# PCB.net
KiCad netlist of a schematic drawn in EasyEDA Pro
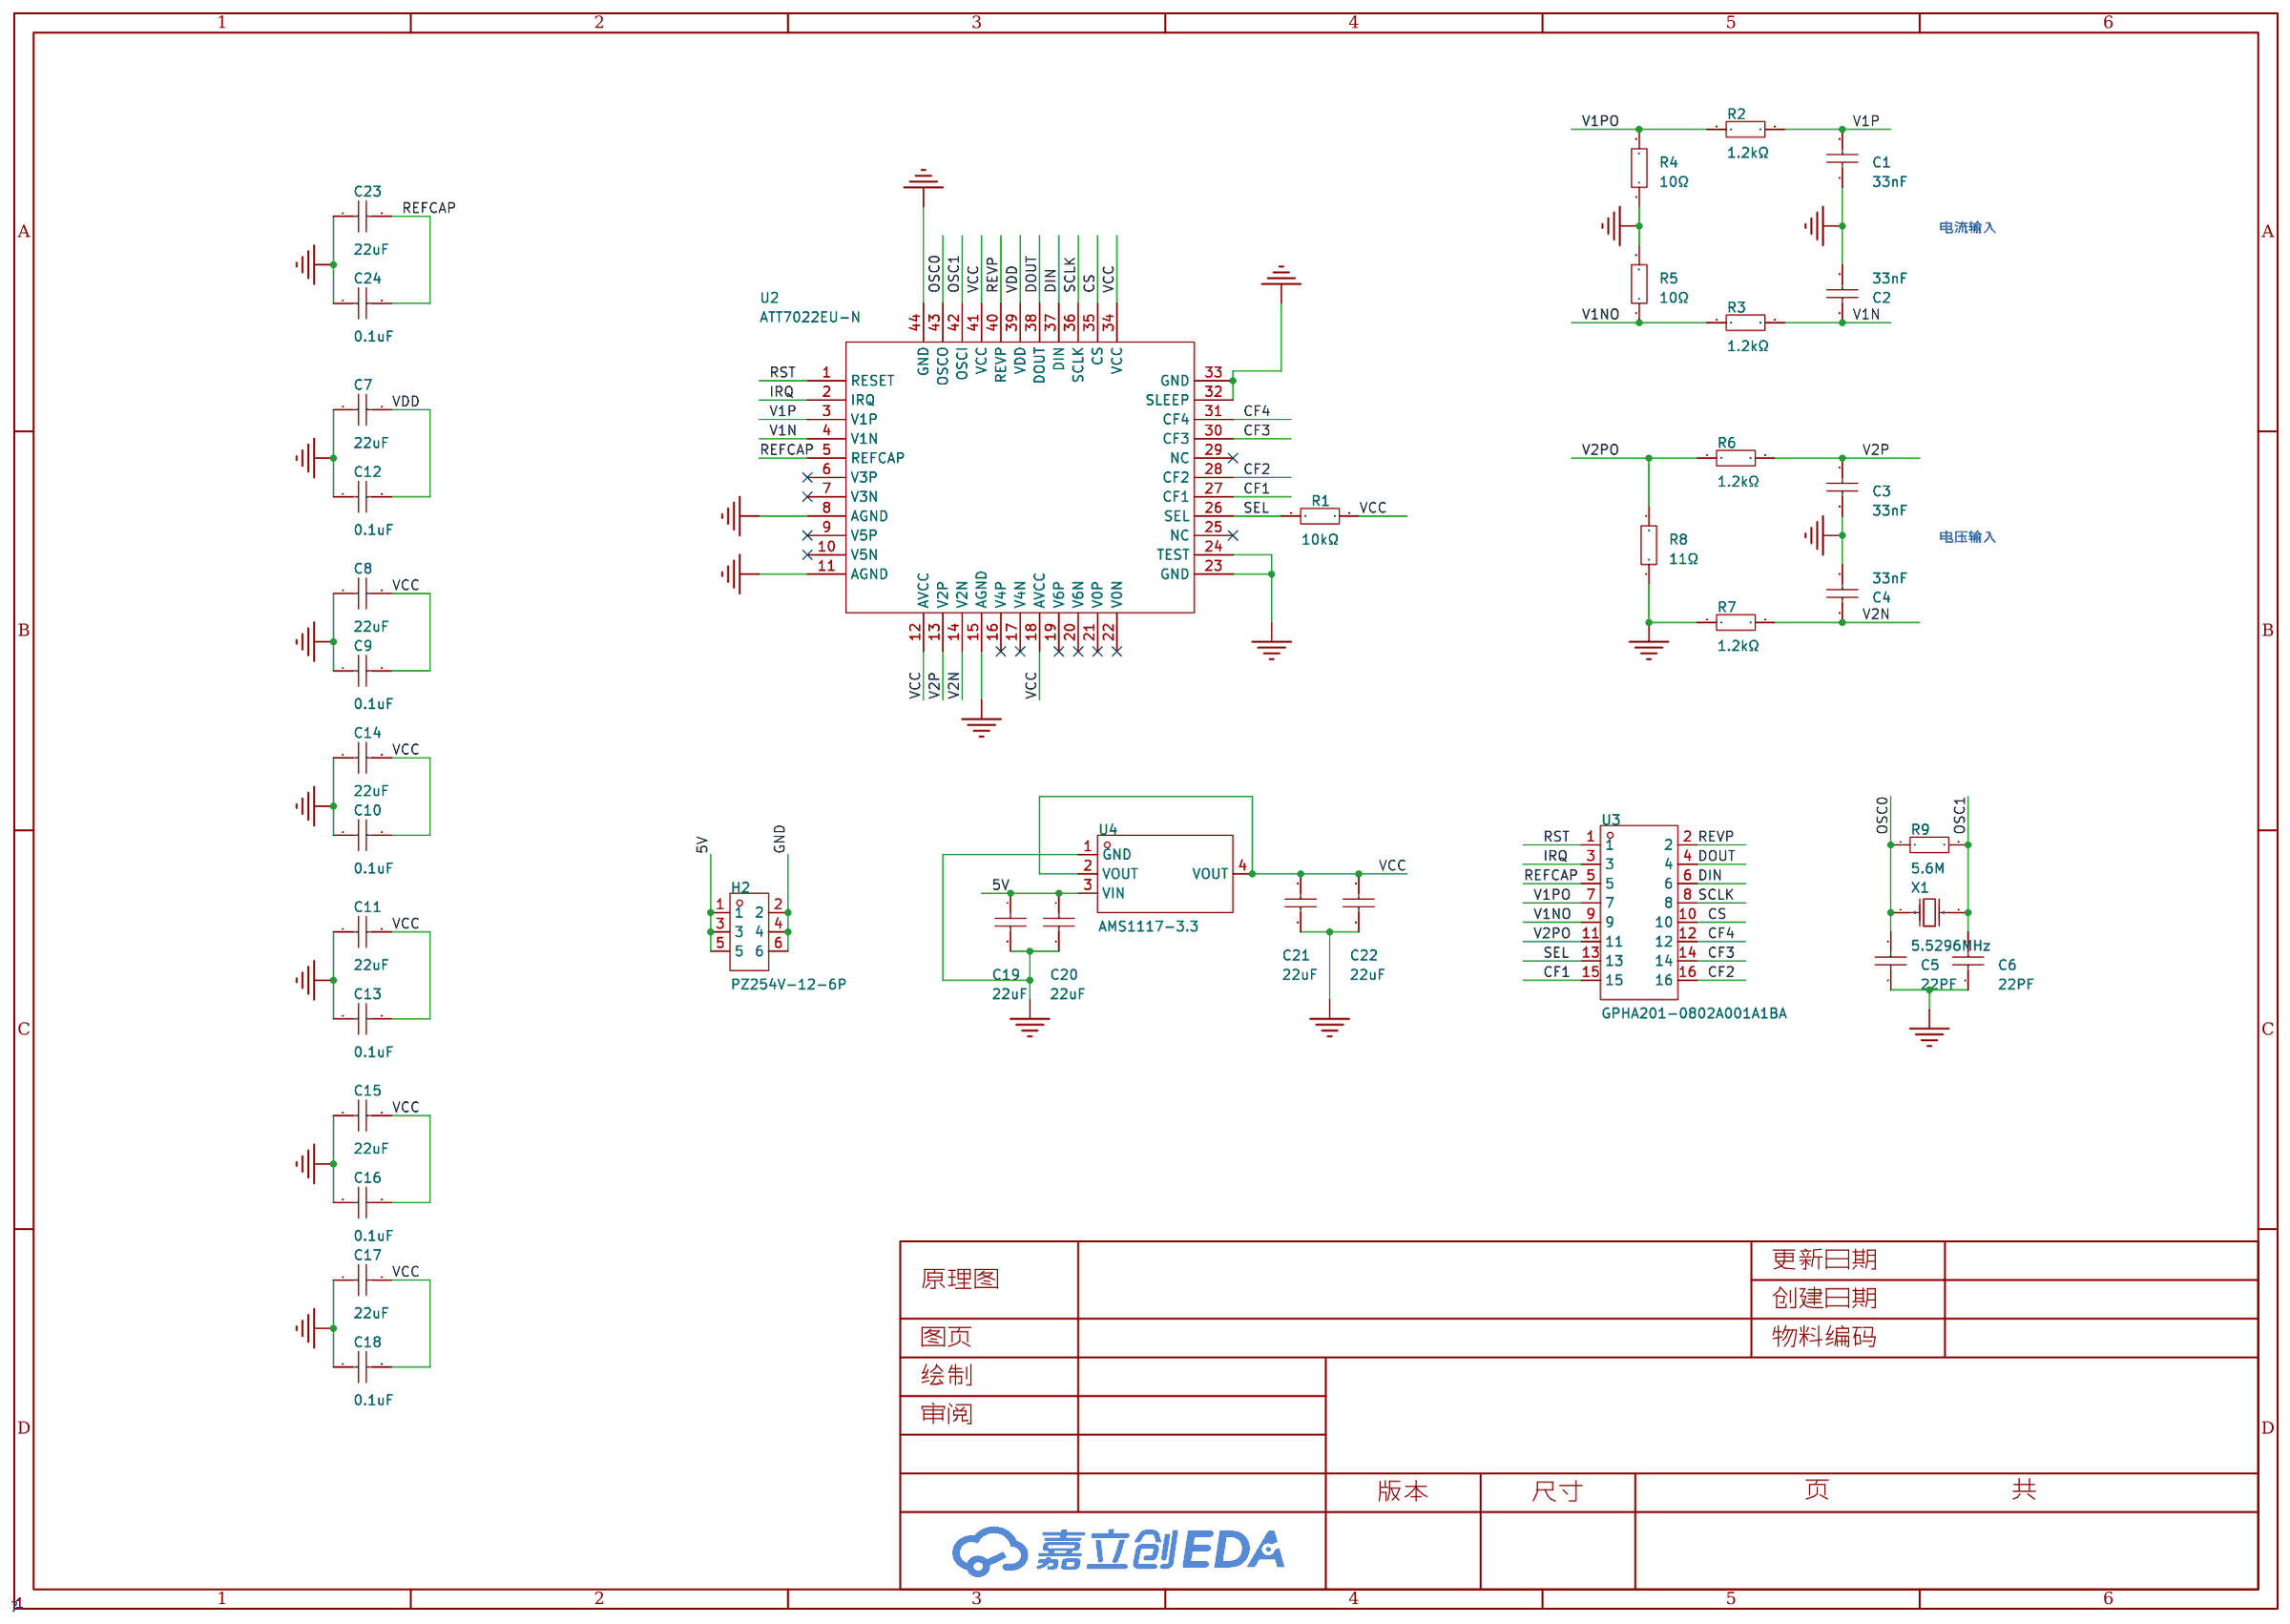
[diagram p0: schematic sheet]

(export (version "E")
  (design (tool "Eeschema 10.0.6"))
  (components
    (comp (ref "C1")
      (value "33nF")
      (footprint "easyedapro:C0805")
      (description "容值:100nF;精度:±10%;额定电压:50V;材质(温度系数):X7R;")
      (fields
        (field (name "Manufacturer Part") "CC0805KRX7R9BB104")
        (field (name "Manufacturer") "YAGEO(国巨)")
      )
      (libsource (lib "easyedapro") (part "CC0805KRX7R9BB104"))
    )
    (comp (ref "C2")
      (value "33nF")
      (footprint "easyedapro:C0805")
      (description "容值:100nF;精度:±10%;额定电压:50V;材质(温度系数):X7R;")
      (fields
        (field (name "Manufacturer Part") "CC0805KRX7R9BB104")
        (field (name "Manufacturer") "YAGEO(国巨)")
      )
      (libsource (lib "easyedapro") (part "CC0805KRX7R9BB104"))
    )
    (comp (ref "C3")
      (value "33nF")
      (footprint "easyedapro:C0805")
      (description "容值:100nF;精度:±10%;额定电压:50V;材质(温度系数):X7R;")
      (fields
        (field (name "Manufacturer Part") "CC0805KRX7R9BB104")
        (field (name "Manufacturer") "YAGEO(国巨)")
      )
      (libsource (lib "easyedapro") (part "CC0805KRX7R9BB104"))
    )
    (comp (ref "C4")
      (value "33nF")
      (footprint "easyedapro:C0805")
      (description "容值:100nF;精度:±10%;额定电压:50V;材质(温度系数):X7R;")
      (fields
        (field (name "Manufacturer Part") "CC0805KRX7R9BB104")
        (field (name "Manufacturer") "YAGEO(国巨)")
      )
      (libsource (lib "easyedapro") (part "CC0805KRX7R9BB104"))
    )
    (comp (ref "C5")
      (value "22PF")
      (footprint "easyedapro:C0805")
      (description "容值:100nF;精度:±10%;额定电压:50V;材质(温度系数):X7R;")
      (fields
        (field (name "Manufacturer Part") "CC0805KRX7R9BB104")
        (field (name "Manufacturer") "YAGEO(国巨)")
      )
      (libsource (lib "easyedapro") (part "CC0805KRX7R9BB104"))
    )
    (comp (ref "C6")
      (value "22PF")
      (footprint "easyedapro:C0805")
      (description "容值:100nF;精度:±10%;额定电压:50V;材质(温度系数):X7R;")
      (fields
        (field (name "Manufacturer Part") "CC0805KRX7R9BB104")
        (field (name "Manufacturer") "YAGEO(国巨)")
      )
      (libsource (lib "easyedapro") (part "CC0805KRX7R9BB104"))
    )
    (comp (ref "C7")
      (value "22uF")
      (footprint "easyedapro:C0805")
      (description "容值:100nF;精度:±10%;额定电压:50V;材质(温度系数):X7R;")
      (fields
        (field (name "Manufacturer Part") "CC0805KRX7R9BB104")
        (field (name "Manufacturer") "YAGEO(国巨)")
      )
      (libsource (lib "easyedapro") (part "CC0805KRX7R9BB104"))
    )
    (comp (ref "C8")
      (value "22uF")
      (footprint "easyedapro:C0805")
      (description "容值:100nF;精度:±10%;额定电压:50V;材质(温度系数):X7R;")
      (fields
        (field (name "Manufacturer Part") "CC0805KRX7R9BB104")
        (field (name "Manufacturer") "YAGEO(国巨)")
      )
      (libsource (lib "easyedapro") (part "CC0805KRX7R9BB104"))
    )
    (comp (ref "C9")
      (value "0.1uF")
      (footprint "easyedapro:C0805")
      (description "容值:100nF;精度:±10%;额定电压:50V;材质(温度系数):X7R;")
      (fields
        (field (name "Manufacturer Part") "CC0805KRX7R9BB104")
        (field (name "Manufacturer") "YAGEO(国巨)")
      )
      (libsource (lib "easyedapro") (part "CC0805KRX7R9BB104"))
    )
    (comp (ref "C10")
      (value "0.1uF")
      (footprint "easyedapro:C0805")
      (description "容值:100nF;精度:±10%;额定电压:50V;材质(温度系数):X7R;")
      (fields
        (field (name "Manufacturer Part") "CC0805KRX7R9BB104")
        (field (name "Manufacturer") "YAGEO(国巨)")
      )
      (libsource (lib "easyedapro") (part "CC0805KRX7R9BB104"))
    )
    (comp (ref "C11")
      (value "22uF")
      (footprint "easyedapro:C0805")
      (description "容值:100nF;精度:±10%;额定电压:50V;材质(温度系数):X7R;")
      (fields
        (field (name "Manufacturer Part") "CC0805KRX7R9BB104")
        (field (name "Manufacturer") "YAGEO(国巨)")
      )
      (libsource (lib "easyedapro") (part "CC0805KRX7R9BB104"))
    )
    (comp (ref "C12")
      (value "0.1uF")
      (footprint "easyedapro:C0805")
      (description "容值:100nF;精度:±10%;额定电压:50V;材质(温度系数):X7R;")
      (fields
        (field (name "Manufacturer Part") "CC0805KRX7R9BB104")
        (field (name "Manufacturer") "YAGEO(国巨)")
      )
      (libsource (lib "easyedapro") (part "CC0805KRX7R9BB104"))
    )
    (comp (ref "C13")
      (value "0.1uF")
      (footprint "easyedapro:C0805")
      (description "容值:100nF;精度:±10%;额定电压:50V;材质(温度系数):X7R;")
      (fields
        (field (name "Manufacturer Part") "CC0805KRX7R9BB104")
        (field (name "Manufacturer") "YAGEO(国巨)")
      )
      (libsource (lib "easyedapro") (part "CC0805KRX7R9BB104"))
    )
    (comp (ref "C14")
      (value "22uF")
      (footprint "easyedapro:C0805")
      (description "容值:100nF;精度:±10%;额定电压:50V;材质(温度系数):X7R;")
      (fields
        (field (name "Manufacturer Part") "CC0805KRX7R9BB104")
        (field (name "Manufacturer") "YAGEO(国巨)")
      )
      (libsource (lib "easyedapro") (part "CC0805KRX7R9BB104"))
    )
    (comp (ref "C15")
      (value "22uF")
      (footprint "easyedapro:C0805")
      (description "容值:100nF;精度:±10%;额定电压:50V;材质(温度系数):X7R;")
      (fields
        (field (name "Manufacturer Part") "CC0805KRX7R9BB104")
        (field (name "Manufacturer") "YAGEO(国巨)")
      )
      (libsource (lib "easyedapro") (part "CC0805KRX7R9BB104"))
    )
    (comp (ref "C16")
      (value "0.1uF")
      (footprint "easyedapro:C0805")
      (description "容值:100nF;精度:±10%;额定电压:50V;材质(温度系数):X7R;")
      (fields
        (field (name "Manufacturer Part") "CC0805KRX7R9BB104")
        (field (name "Manufacturer") "YAGEO(国巨)")
      )
      (libsource (lib "easyedapro") (part "CC0805KRX7R9BB104"))
    )
    (comp (ref "C17")
      (value "22uF")
      (footprint "easyedapro:C0805")
      (description "容值:100nF;精度:±10%;额定电压:50V;材质(温度系数):X7R;")
      (fields
        (field (name "Manufacturer Part") "CC0805KRX7R9BB104")
        (field (name "Manufacturer") "YAGEO(国巨)")
      )
      (libsource (lib "easyedapro") (part "CC0805KRX7R9BB104"))
    )
    (comp (ref "C18")
      (value "0.1uF")
      (footprint "easyedapro:C0805")
      (description "容值:100nF;精度:±10%;额定电压:50V;材质(温度系数):X7R;")
      (fields
        (field (name "Manufacturer Part") "CC0805KRX7R9BB104")
        (field (name "Manufacturer") "YAGEO(国巨)")
      )
      (libsource (lib "easyedapro") (part "CC0805KRX7R9BB104"))
    )
    (comp (ref "C19")
      (value "22uF")
      (footprint "easyedapro:C0805")
      (description "容值:100nF;精度:±10%;额定电压:50V;材质(温度系数):X7R;")
      (fields
        (field (name "Manufacturer Part") "CC0805KRX7R9BB104")
        (field (name "Manufacturer") "YAGEO(国巨)")
      )
      (libsource (lib "easyedapro") (part "CC0805KRX7R9BB104"))
    )
    (comp (ref "C20")
      (value "22uF")
      (footprint "easyedapro:C0805")
      (description "容值:100nF;精度:±10%;额定电压:50V;材质(温度系数):X7R;")
      (fields
        (field (name "Manufacturer Part") "CC0805KRX7R9BB104")
        (field (name "Manufacturer") "YAGEO(国巨)")
      )
      (libsource (lib "easyedapro") (part "CC0805KRX7R9BB104"))
    )
    (comp (ref "C21")
      (value "22uF")
      (footprint "easyedapro:C0805")
      (description "容值:100nF;精度:±10%;额定电压:50V;材质(温度系数):X7R;")
      (fields
        (field (name "Manufacturer Part") "CC0805KRX7R9BB104")
        (field (name "Manufacturer") "YAGEO(国巨)")
      )
      (libsource (lib "easyedapro") (part "CC0805KRX7R9BB104"))
    )
    (comp (ref "C22")
      (value "22uF")
      (footprint "easyedapro:C0805")
      (description "容值:100nF;精度:±10%;额定电压:50V;材质(温度系数):X7R;")
      (fields
        (field (name "Manufacturer Part") "CC0805KRX7R9BB104")
        (field (name "Manufacturer") "YAGEO(国巨)")
      )
      (libsource (lib "easyedapro") (part "CC0805KRX7R9BB104"))
    )
    (comp (ref "C23")
      (value "22uF")
      (footprint "easyedapro:C0805")
      (description "容值:100nF;精度:±10%;额定电压:50V;材质(温度系数):X7R;")
      (fields
        (field (name "Manufacturer Part") "CC0805KRX7R9BB104")
        (field (name "Manufacturer") "YAGEO(国巨)")
      )
      (libsource (lib "easyedapro") (part "CC0805KRX7R9BB104"))
    )
    (comp (ref "C24")
      (value "0.1uF")
      (footprint "easyedapro:C0805")
      (description "容值:100nF;精度:±10%;额定电压:50V;材质(温度系数):X7R;")
      (fields
        (field (name "Manufacturer Part") "CC0805KRX7R9BB104")
        (field (name "Manufacturer") "YAGEO(国巨)")
      )
      (libsource (lib "easyedapro") (part "CC0805KRX7R9BB104"))
    )
    (comp (ref "H2")
      (value "PZ254V-12-6P")
      (footprint "easyedapro:HDR-TH_6P-P2.54-V-M-R2-C3-S2.54")
      (fields (field (name "Manufacturer") "XFCN(兴飞)"))
      (libsource (lib "easyedapro") (part "PZ254V-12-6P"))
    )
    (comp (ref "R1")
      (value "10kΩ")
      (footprint "easyedapro:R0805")
      (description "电阻类型:厚膜电阻;阻值:10kΩ;精度:±1%;功率:125mW;最大工作电压:150V;温度系数:±100ppm/°C;")
      (fields
        (field (name "Manufacturer Part") "0805W8F1002T5E")
        (field (name "Manufacturer") "UNI-ROYAL(厚声)")
      )
      (libsource (lib "easyedapro") (part "0805W8F1002T5E"))
    )
    (comp (ref "R2")
      (value "1.2kΩ")
      (footprint "easyedapro:R0805")
      (description "电阻类型:厚膜电阻;阻值:10kΩ;精度:±1%;功率:125mW;最大工作电压:150V;温度系数:±100ppm/°C;")
      (fields
        (field (name "Manufacturer Part") "0805W8F1002T5E")
        (field (name "Manufacturer") "UNI-ROYAL(厚声)")
      )
      (libsource (lib "easyedapro") (part "0805W8F1002T5E"))
    )
    (comp (ref "R3")
      (value "1.2kΩ")
      (footprint "easyedapro:R0805")
      (description "电阻类型:厚膜电阻;阻值:10kΩ;精度:±1%;功率:125mW;最大工作电压:150V;温度系数:±100ppm/°C;")
      (fields
        (field (name "Manufacturer Part") "0805W8F1002T5E")
        (field (name "Manufacturer") "UNI-ROYAL(厚声)")
      )
      (libsource (lib "easyedapro") (part "0805W8F1002T5E"))
    )
    (comp (ref "R4")
      (value "10Ω")
      (footprint "easyedapro:R0805")
      (description "电阻类型:厚膜电阻;阻值:10kΩ;精度:±1%;功率:125mW;最大工作电压:150V;温度系数:±100ppm/°C;")
      (fields
        (field (name "Manufacturer Part") "0805W8F1002T5E")
        (field (name "Manufacturer") "UNI-ROYAL(厚声)")
      )
      (libsource (lib "easyedapro") (part "0805W8F1002T5E"))
    )
    (comp (ref "R5")
      (value "10Ω")
      (footprint "easyedapro:R0805")
      (description "电阻类型:厚膜电阻;阻值:10kΩ;精度:±1%;功率:125mW;最大工作电压:150V;温度系数:±100ppm/°C;")
      (fields
        (field (name "Manufacturer Part") "0805W8F1002T5E")
        (field (name "Manufacturer") "UNI-ROYAL(厚声)")
      )
      (libsource (lib "easyedapro") (part "0805W8F1002T5E"))
    )
    (comp (ref "R6")
      (value "1.2kΩ")
      (footprint "easyedapro:R0805")
      (description "电阻类型:厚膜电阻;阻值:10kΩ;精度:±1%;功率:125mW;最大工作电压:150V;温度系数:±100ppm/°C;")
      (fields
        (field (name "Manufacturer Part") "0805W8F1002T5E")
        (field (name "Manufacturer") "UNI-ROYAL(厚声)")
      )
      (libsource (lib "easyedapro") (part "0805W8F1002T5E"))
    )
    (comp (ref "R7")
      (value "1.2kΩ")
      (footprint "easyedapro:R0805")
      (description "电阻类型:厚膜电阻;阻值:10kΩ;精度:±1%;功率:125mW;最大工作电压:150V;温度系数:±100ppm/°C;")
      (fields
        (field (name "Manufacturer Part") "0805W8F1002T5E")
        (field (name "Manufacturer") "UNI-ROYAL(厚声)")
      )
      (libsource (lib "easyedapro") (part "0805W8F1002T5E"))
    )
    (comp (ref "R8")
      (value "11Ω")
      (footprint "easyedapro:R0805")
      (description "电阻类型:厚膜电阻;阻值:10kΩ;精度:±1%;功率:125mW;最大工作电压:150V;温度系数:±100ppm/°C;")
      (fields
        (field (name "Manufacturer Part") "0805W8F1002T5E")
        (field (name "Manufacturer") "UNI-ROYAL(厚声)")
      )
      (libsource (lib "easyedapro") (part "0805W8F1002T5E"))
    )
    (comp (ref "R9")
      (value "5.6M")
      (footprint "easyedapro:R0805")
      (description "电阻类型:厚膜电阻;阻值:10kΩ;精度:±1%;功率:125mW;最大工作电压:150V;温度系数:±100ppm/°C;")
      (fields
        (field (name "Manufacturer Part") "0805W8F1002T5E")
        (field (name "Manufacturer") "UNI-ROYAL(厚声)")
      )
      (libsource (lib "easyedapro") (part "0805W8F1002T5E"))
    )
    (comp (ref "U2")
      (value "ATT7022EU-N")
      (footprint "easyedapro:LQFP-44_L10.0-W10.0-P0.80-LS12.0-BL")
      (fields (field (name "Manufacturer") "钜泉光电"))
      (libsource (lib "easyedapro") (part "ATT7022EU"))
    )
    (comp (ref "U3")
      (value "GPHA201-0802A001A1BA")
      (footprint "easyedapro:HDR-TH_16P-P2.54-V-M-R2-C8-S2.54")
      (description "插针结构:2x8P;间距:2.54mm;行距:2.54mm;圆针/方针:方针;安装类型:直插;排数:双排;总PIN位数:16P;额定电流:3A;工作温度范围:-40°C~+105°C;")
      (fields (field (name "Manufacturer") "GREENCONN(格康)"))
      (libsource (lib "easyedapro") (part "GPHA201-0802A001A1BA"))
    )
    (comp (ref "U4")
      (value "AMS1117-3.3")
      (footprint "easyedapro:SOT-223-3_L6.5-W3.4-P2.30-LS7.0-BR")
      (description "输出类型:固定;最大输入电压:-;输出电压:3.3V;最大输出电流:1A;电源纹波抑制比(PSRR):72dB@(120Hz);输出极性:正极;")
      (fields (field (name "Manufacturer") "AMS"))
      (libsource (lib "easyedapro") (part "AMS1117-3.3"))
    )
    (comp (ref "X1")
      (value "5.5296MHz")
      (footprint "easyedapro:HC-49S_L11.4-W4.8-LS12.7")
      (description "晶振类型:贴片晶振;频率:5.5296MHz;常温频差:±20ppm;外接负载电容:20pF;频率稳定度(全温):±30ppm;")
      (fields
        (field (name "Manufacturer Part") "H6OEL89CSC-SUGYLC-5.5296M")
        (field (name "Manufacturer") "YXC(扬兴晶振)")
      )
      (libsource (lib "easyedapro") (part "H6OEL89CSC-SUGYLC-5.5296M"))
    )
  )
  (nets
    (net (code "1") (name "/5V") (class "Default")
      (node (ref "C19") (pin "1") (pinfunction "1_1") (pintype "input"))
      (node (ref "C20") (pin "1") (pinfunction "1_1") (pintype "input"))
      (node (ref "H2") (pin "1") (pinfunction "1_1") (pintype "unspecified"))
      (node (ref "H2") (pin "3") (pinfunction "3_3") (pintype "unspecified"))
      (node (ref "H2") (pin "5") (pinfunction "5_5") (pintype "unspecified"))
      (node (ref "U4") (pin "3") (pinfunction "VIN_3") (pintype "unspecified"))
    )
    (net (code "2") (name "/CF1") (class "Default")
      (node (ref "U2") (pin "27") (pinfunction "CF1_27") (pintype "unspecified"))
      (node (ref "U3") (pin "15") (pinfunction "15_15") (pintype "unspecified"))
    )
    (net (code "3") (name "/CF2") (class "Default")
      (node (ref "U2") (pin "28") (pinfunction "CF2_28") (pintype "unspecified"))
      (node (ref "U3") (pin "16") (pinfunction "16_16") (pintype "unspecified"))
    )
    (net (code "4") (name "/CF3") (class "Default")
      (node (ref "U2") (pin "30") (pinfunction "CF3_30") (pintype "unspecified"))
      (node (ref "U3") (pin "14") (pinfunction "14_14") (pintype "unspecified"))
    )
    (net (code "5") (name "/CF4") (class "Default")
      (node (ref "U2") (pin "31") (pinfunction "CF4_31") (pintype "unspecified"))
      (node (ref "U3") (pin "12") (pinfunction "12_12") (pintype "unspecified"))
    )
    (net (code "6") (name "/CS") (class "Default")
      (node (ref "U2") (pin "35") (pinfunction "CS_35") (pintype "unspecified"))
      (node (ref "U3") (pin "10") (pinfunction "10_10") (pintype "unspecified"))
    )
    (net (code "7") (name "/DIN") (class "Default")
      (node (ref "U2") (pin "37") (pinfunction "DIN_37") (pintype "unspecified"))
      (node (ref "U3") (pin "6") (pinfunction "6_6") (pintype "unspecified"))
    )
    (net (code "8") (name "/DOUT") (class "Default")
      (node (ref "U2") (pin "38") (pinfunction "DOUT_38") (pintype "unspecified"))
      (node (ref "U3") (pin "4") (pinfunction "4_4") (pintype "unspecified"))
    )
    (net (code "9") (name "/IRQ") (class "Default")
      (node (ref "U2") (pin "2") (pinfunction "IRQ_2") (pintype "unspecified"))
      (node (ref "U3") (pin "3") (pinfunction "3_3") (pintype "unspecified"))
    )
    (net (code "10") (name "/OSC0") (class "Default")
      (node (ref "C5") (pin "2") (pinfunction "2_2") (pintype "input"))
      (node (ref "R9") (pin "1") (pinfunction "1_1") (pintype "input"))
      (node (ref "U2") (pin "43") (pinfunction "OSCO_43") (pintype "unspecified"))
      (node (ref "X1") (pin "1") (pinfunction "OSC1_1") (pintype "input"))
    )
    (net (code "11") (name "/OSC1") (class "Default")
      (node (ref "C6") (pin "2") (pinfunction "2_2") (pintype "input"))
      (node (ref "R9") (pin "2") (pinfunction "2_2") (pintype "input"))
      (node (ref "U2") (pin "42") (pinfunction "OSCI_42") (pintype "unspecified"))
      (node (ref "X1") (pin "2") (pinfunction "OSC2_2") (pintype "input"))
    )
    (net (code "12") (name "/REFCAP") (class "Default")
      (node (ref "C23") (pin "1") (pinfunction "1_1") (pintype "input"))
      (node (ref "C24") (pin "1") (pinfunction "1_1") (pintype "input"))
      (node (ref "U2") (pin "5") (pinfunction "REFCAP_5") (pintype "unspecified"))
      (node (ref "U3") (pin "5") (pinfunction "5_5") (pintype "unspecified"))
    )
    (net (code "13") (name "/REVP") (class "Default")
      (node (ref "U2") (pin "40") (pinfunction "REVP_40") (pintype "unspecified"))
      (node (ref "U3") (pin "2") (pinfunction "2_2") (pintype "unspecified"))
    )
    (net (code "14") (name "/RST") (class "Default")
      (node (ref "U2") (pin "1") (pinfunction "RESET_1") (pintype "unspecified"))
      (node (ref "U3") (pin "1") (pinfunction "1_1") (pintype "unspecified"))
    )
    (net (code "15") (name "/SCLK") (class "Default")
      (node (ref "U2") (pin "36") (pinfunction "SCLK_36") (pintype "unspecified"))
      (node (ref "U3") (pin "8") (pinfunction "8_8") (pintype "unspecified"))
    )
    (net (code "16") (name "/SEL") (class "Default")
      (node (ref "R1") (pin "1") (pinfunction "1_1") (pintype "input"))
      (node (ref "U2") (pin "26") (pinfunction "SEL_26") (pintype "unspecified"))
      (node (ref "U3") (pin "13") (pinfunction "13_13") (pintype "unspecified"))
    )
    (net (code "17") (name "/V1N") (class "Default")
      (node (ref "C2") (pin "1") (pinfunction "1_1") (pintype "input"))
      (node (ref "R3") (pin "2") (pinfunction "2_2") (pintype "input"))
      (node (ref "U2") (pin "4") (pinfunction "V1N_4") (pintype "unspecified"))
    )
    (net (code "18") (name "/V1NO") (class "Default")
      (node (ref "R3") (pin "1") (pinfunction "1_1") (pintype "input"))
      (node (ref "R5") (pin "1") (pinfunction "1_1") (pintype "input"))
      (node (ref "U3") (pin "9") (pinfunction "9_9") (pintype "unspecified"))
    )
    (net (code "19") (name "/V1P") (class "Default")
      (node (ref "C1") (pin "2") (pinfunction "2_2") (pintype "input"))
      (node (ref "R2") (pin "2") (pinfunction "2_2") (pintype "input"))
      (node (ref "U2") (pin "3") (pinfunction "V1P_3") (pintype "unspecified"))
    )
    (net (code "20") (name "/V1PO") (class "Default")
      (node (ref "R2") (pin "1") (pinfunction "1_1") (pintype "input"))
      (node (ref "R4") (pin "2") (pinfunction "2_2") (pintype "input"))
      (node (ref "U3") (pin "7") (pinfunction "7_7") (pintype "unspecified"))
    )
    (net (code "21") (name "/V2N") (class "Default")
      (node (ref "C4") (pin "1") (pinfunction "1_1") (pintype "input"))
      (node (ref "R7") (pin "2") (pinfunction "2_2") (pintype "input"))
      (node (ref "U2") (pin "14") (pinfunction "V2N_14") (pintype "unspecified"))
    )
    (net (code "22") (name "/V2P") (class "Default")
      (node (ref "C3") (pin "2") (pinfunction "2_2") (pintype "input"))
      (node (ref "R6") (pin "2") (pinfunction "2_2") (pintype "input"))
      (node (ref "U2") (pin "13") (pinfunction "V2P_13") (pintype "unspecified"))
    )
    (net (code "23") (name "/V2PO") (class "Default")
      (node (ref "R6") (pin "1") (pinfunction "1_1") (pintype "input"))
      (node (ref "R8") (pin "2") (pinfunction "2_2") (pintype "input"))
      (node (ref "U3") (pin "11") (pinfunction "11_11") (pintype "unspecified"))
    )
    (net (code "24") (name "/VCC") (class "Default")
      (node (ref "C10") (pin "1") (pinfunction "1_1") (pintype "input"))
      (node (ref "C11") (pin "1") (pinfunction "1_1") (pintype "input"))
      (node (ref "C13") (pin "1") (pinfunction "1_1") (pintype "input"))
      (node (ref "C14") (pin "1") (pinfunction "1_1") (pintype "input"))
      (node (ref "C15") (pin "1") (pinfunction "1_1") (pintype "input"))
      (node (ref "C16") (pin "1") (pinfunction "1_1") (pintype "input"))
      (node (ref "C17") (pin "1") (pinfunction "1_1") (pintype "input"))
      (node (ref "C18") (pin "1") (pinfunction "1_1") (pintype "input"))
      (node (ref "C21") (pin "1") (pinfunction "1_1") (pintype "input"))
      (node (ref "C22") (pin "1") (pinfunction "1_1") (pintype "input"))
      (node (ref "C8") (pin "1") (pinfunction "1_1") (pintype "input"))
      (node (ref "C9") (pin "1") (pinfunction "1_1") (pintype "input"))
      (node (ref "R1") (pin "2") (pinfunction "2_2") (pintype "input"))
      (node (ref "U2") (pin "12") (pinfunction "AVCC_12") (pintype "unspecified"))
      (node (ref "U2") (pin "18") (pinfunction "AVCC_18") (pintype "unspecified"))
      (node (ref "U2") (pin "34") (pinfunction "VCC_34") (pintype "unspecified"))
      (node (ref "U2") (pin "41") (pinfunction "VCC_41") (pintype "unspecified"))
      (node (ref "U4") (pin "2") (pinfunction "VOUT_2") (pintype "unspecified"))
      (node (ref "U4") (pin "4") (pinfunction "VOUT_4") (pintype "unspecified"))
    )
    (net (code "25") (name "/VDD") (class "Default")
      (node (ref "C12") (pin "1") (pinfunction "1_1") (pintype "input"))
      (node (ref "C7") (pin "1") (pinfunction "1_1") (pintype "input"))
      (node (ref "U2") (pin "39") (pinfunction "VDD_39") (pintype "unspecified"))
    )
    (net (code "26") (name "GND") (class "Default")
      (node (ref "C1") (pin "1") (pinfunction "1_1") (pintype "input"))
      (node (ref "C10") (pin "2") (pinfunction "2_2") (pintype "input"))
      (node (ref "C11") (pin "2") (pinfunction "2_2") (pintype "input"))
      (node (ref "C12") (pin "2") (pinfunction "2_2") (pintype "input"))
      (node (ref "C13") (pin "2") (pinfunction "2_2") (pintype "input"))
      (node (ref "C14") (pin "2") (pinfunction "2_2") (pintype "input"))
      (node (ref "C15") (pin "2") (pinfunction "2_2") (pintype "input"))
      (node (ref "C16") (pin "2") (pinfunction "2_2") (pintype "input"))
      (node (ref "C17") (pin "2") (pinfunction "2_2") (pintype "input"))
      (node (ref "C18") (pin "2") (pinfunction "2_2") (pintype "input"))
      (node (ref "C19") (pin "2") (pinfunction "2_2") (pintype "input"))
      (node (ref "C2") (pin "2") (pinfunction "2_2") (pintype "input"))
      (node (ref "C20") (pin "2") (pinfunction "2_2") (pintype "input"))
      (node (ref "C21") (pin "2") (pinfunction "2_2") (pintype "input"))
      (node (ref "C22") (pin "2") (pinfunction "2_2") (pintype "input"))
      (node (ref "C23") (pin "2") (pinfunction "2_2") (pintype "input"))
      (node (ref "C24") (pin "2") (pinfunction "2_2") (pintype "input"))
      (node (ref "C3") (pin "1") (pinfunction "1_1") (pintype "input"))
      (node (ref "C4") (pin "2") (pinfunction "2_2") (pintype "input"))
      (node (ref "C5") (pin "1") (pinfunction "1_1") (pintype "input"))
      (node (ref "C6") (pin "1") (pinfunction "1_1") (pintype "input"))
      (node (ref "C7") (pin "2") (pinfunction "2_2") (pintype "input"))
      (node (ref "C8") (pin "2") (pinfunction "2_2") (pintype "input"))
      (node (ref "C9") (pin "2") (pinfunction "2_2") (pintype "input"))
      (node (ref "H2") (pin "2") (pinfunction "2_2") (pintype "unspecified"))
      (node (ref "H2") (pin "4") (pinfunction "4_4") (pintype "unspecified"))
      (node (ref "H2") (pin "6") (pinfunction "6_6") (pintype "unspecified"))
      (node (ref "R4") (pin "1") (pinfunction "1_1") (pintype "input"))
      (node (ref "R5") (pin "2") (pinfunction "2_2") (pintype "input"))
      (node (ref "R7") (pin "1") (pinfunction "1_1") (pintype "input"))
      (node (ref "R8") (pin "1") (pinfunction "1_1") (pintype "input"))
      (node (ref "U2") (pin "11") (pinfunction "AGND_11") (pintype "unspecified"))
      (node (ref "U2") (pin "15") (pinfunction "AGND_15") (pintype "unspecified"))
      (node (ref "U2") (pin "23") (pinfunction "GND_23") (pintype "unspecified"))
      (node (ref "U2") (pin "24") (pinfunction "TEST_24") (pintype "unspecified"))
      (node (ref "U2") (pin "32") (pinfunction "SLEEP_32") (pintype "unspecified"))
      (node (ref "U2") (pin "33") (pinfunction "GND_33") (pintype "unspecified"))
      (node (ref "U2") (pin "44") (pinfunction "GND_44") (pintype "unspecified"))
      (node (ref "U2") (pin "8") (pinfunction "AGND_8") (pintype "unspecified"))
      (node (ref "U4") (pin "1") (pinfunction "GND_1") (pintype "unspecified"))
    )
    (net (code "27") (name "unconnected-(U2-NC-Pad25)") (class "Default")
      (node (ref "U2") (pin "25") (pinfunction "NC_25") (pintype "unspecified+no_connect"))
    )
    (net (code "28") (name "unconnected-(U2-NC-Pad29)") (class "Default")
      (node (ref "U2") (pin "29") (pinfunction "NC_29") (pintype "unspecified+no_connect"))
    )
    (net (code "29") (name "unconnected-(U2-V0N-Pad22)") (class "Default")
      (node (ref "U2") (pin "22") (pinfunction "V0N_22") (pintype "unspecified+no_connect"))
    )
    (net (code "30") (name "unconnected-(U2-V0P-Pad21)") (class "Default")
      (node (ref "U2") (pin "21") (pinfunction "V0P_21") (pintype "unspecified+no_connect"))
    )
    (net (code "31") (name "unconnected-(U2-V3N-Pad7)") (class "Default")
      (node (ref "U2") (pin "7") (pinfunction "V3N_7") (pintype "unspecified+no_connect"))
    )
    (net (code "32") (name "unconnected-(U2-V3P-Pad6)") (class "Default")
      (node (ref "U2") (pin "6") (pinfunction "V3P_6") (pintype "unspecified+no_connect"))
    )
    (net (code "33") (name "unconnected-(U2-V4N-Pad17)") (class "Default")
      (node (ref "U2") (pin "17") (pinfunction "V4N_17") (pintype "unspecified+no_connect"))
    )
    (net (code "34") (name "unconnected-(U2-V4P-Pad16)") (class "Default")
      (node (ref "U2") (pin "16") (pinfunction "V4P_16") (pintype "unspecified+no_connect"))
    )
    (net (code "35") (name "unconnected-(U2-V5N-Pad10)") (class "Default")
      (node (ref "U2") (pin "10") (pinfunction "V5N_10") (pintype "unspecified+no_connect"))
    )
    (net (code "36") (name "unconnected-(U2-V5P-Pad9)") (class "Default")
      (node (ref "U2") (pin "9") (pinfunction "V5P_9") (pintype "unspecified+no_connect"))
    )
    (net (code "37") (name "unconnected-(U2-V6N-Pad20)") (class "Default")
      (node (ref "U2") (pin "20") (pinfunction "V6N_20") (pintype "unspecified+no_connect"))
    )
    (net (code "38") (name "unconnected-(U2-V6P-Pad19)") (class "Default")
      (node (ref "U2") (pin "19") (pinfunction "V6P_19") (pintype "unspecified+no_connect"))
    )
  )
)
